# PlacaBase.net
KiCad netlist of a schematic drawn in EAGLE
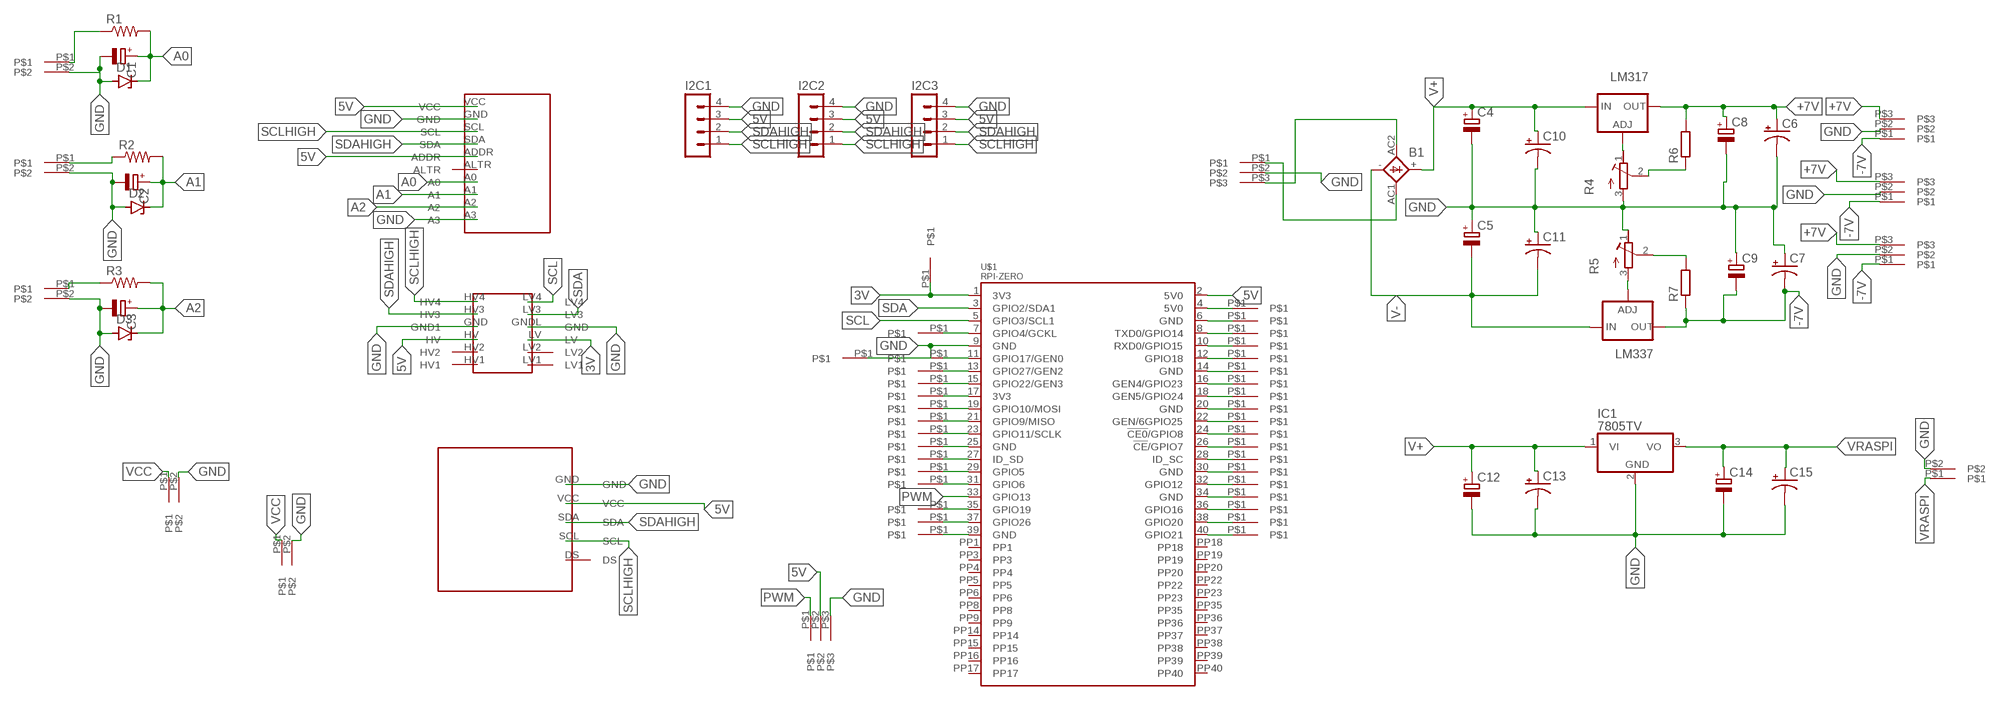
[diagram p0: schematic, sheet 1]

(export (version "E")
  (design (tool "Eeschema 10.0.6"))
  (components
    (comp (ref "5VIN")
      (value "MOLEXPEQUEÑO2P")
      (footprint "eagle-import:MOLEXPEQUEÑO2P")
      (libsource (lib "eagle-import") (part "MOLEXPEQUEÑO2P"))
    )
    (comp (ref "B1")
      (value "KBL")
      (footprint "eagle-import:KBL")
      (libsource (lib "eagle-import") (part "KBL"))
    )
    (comp (ref "C1")
      (value "CPOL-EUE5-5")
      (footprint "eagle-import:E5-5")
      (libsource (lib "eagle-import") (part "CPOL-EUE5-5"))
    )
    (comp (ref "C2")
      (value "CPOL-EUE5-5")
      (footprint "eagle-import:E5-5")
      (libsource (lib "eagle-import") (part "CPOL-EUE5-5"))
    )
    (comp (ref "C3")
      (value "CPOL-EUE5-5")
      (footprint "eagle-import:E5-5")
      (libsource (lib "eagle-import") (part "CPOL-EUE5-5"))
    )
    (comp (ref "C4")
      (value "CPOL-EUE3.5-10")
      (footprint "eagle-import:E3,5-10")
      (libsource (lib "eagle-import") (part "R Pad Grand_CPOL-EUE3.5-10"))
    )
    (comp (ref "C5")
      (value "CPOL-EUE3.5-10")
      (footprint "eagle-import:E3,5-10")
      (libsource (lib "eagle-import") (part "R Pad Grand_CPOL-EUE3.5-10"))
    )
    (comp (ref "C6")
      (value "CPOL-USTAP5-45")
      (footprint "eagle-import:TAP5-45")
      (libsource (lib "eagle-import") (part "CPOL-USTAP5-45"))
    )
    (comp (ref "C7")
      (value "CPOL-USTAP5-45")
      (footprint "eagle-import:TAP5-45")
      (libsource (lib "eagle-import") (part "CPOL-USTAP5-45"))
    )
    (comp (ref "C8")
      (value "CPOL-EUTT2D7")
      (footprint "eagle-import:TT2D7")
      (libsource (lib "eagle-import") (part "R Pad Grand_CPOL-EUTT2D7"))
    )
    (comp (ref "C9")
      (value "CPOL-EUTT2D7")
      (footprint "eagle-import:TT2D7")
      (libsource (lib "eagle-import") (part "R Pad Grand_CPOL-EUTT2D7"))
    )
    (comp (ref "C10")
      (value "CPOL-USTAP5-45")
      (footprint "eagle-import:TAP5-45")
      (libsource (lib "eagle-import") (part "CPOL-USTAP5-45"))
    )
    (comp (ref "C11")
      (value "CPOL-USTAP5-45")
      (footprint "eagle-import:TAP5-45")
      (libsource (lib "eagle-import") (part "CPOL-USTAP5-45"))
    )
    (comp (ref "C12")
      (value "CPOL-EUE3.5-10")
      (footprint "eagle-import:E3,5-10")
      (libsource (lib "eagle-import") (part "R Pad Grand_CPOL-EUE3.5-10"))
    )
    (comp (ref "C13")
      (value "CPOL-USTAP5-45")
      (footprint "eagle-import:TAP5-45")
      (libsource (lib "eagle-import") (part "CPOL-USTAP5-45"))
    )
    (comp (ref "C14")
      (value "CPOL-EUTT2D7")
      (footprint "eagle-import:TT2D7")
      (libsource (lib "eagle-import") (part "R Pad Grand_CPOL-EUTT2D7"))
    )
    (comp (ref "C15")
      (value "CPOL-USTAP5-45")
      (footprint "eagle-import:TAP5-45")
      (libsource (lib "eagle-import") (part "CPOL-USTAP5-45"))
    )
    (comp (ref "D1")
      (value "ZENER-DIODEDO34-7")
      (footprint "eagle-import:DO34Z7")
      (libsource (lib "eagle-import") (part "ZENER-DIODEDO34-7"))
    )
    (comp (ref "D2")
      (value "ZENER-DIODEDO34-7")
      (footprint "eagle-import:DO34Z7")
      (libsource (lib "eagle-import") (part "ZENER-DIODEDO34-7"))
    )
    (comp (ref "D3")
      (value "ZENER-DIODEDO34-7")
      (footprint "eagle-import:DO34Z7")
      (libsource (lib "eagle-import") (part "ZENER-DIODEDO34-7"))
    )
    (comp (ref "ENTRADAAC")
      (value "MOLEXPEQUEÑO")
      (footprint "eagle-import:MOLEXPEQUEÑO")
      (libsource (lib "eagle-import") (part "MOLEXPEQUEÑO"))
    )
    (comp (ref "I2C1")
      (value "MA04-1")
      (footprint "eagle-import:MA04-1")
      (libsource (lib "eagle-import") (part "MA04-1"))
    )
    (comp (ref "I2C2")
      (value "MA04-1")
      (footprint "eagle-import:MA04-1")
      (libsource (lib "eagle-import") (part "MA04-1"))
    )
    (comp (ref "I2C3")
      (value "MA04-1")
      (footprint "eagle-import:MA04-1")
      (libsource (lib "eagle-import") (part "MA04-1"))
    )
    (comp (ref "IC1")
      (value "7805TV")
      (footprint "eagle-import:TO220V")
      (libsource (lib "eagle-import") (part "78TV05"))
    )
    (comp (ref "LM317")
      (value "LM317TS")
      (footprint "eagle-import:317TS")
      (libsource (lib "eagle-import") (part "LM317TS"))
    )
    (comp (ref "LM337")
      (value "LM337TS")
      (footprint "eagle-import:337TS")
      (libsource (lib "eagle-import") (part "LM337TS"))
    )
    (comp (ref "R1")
      (value "R-US_0204/5")
      (footprint "eagle-import:0204_5")
      (libsource (lib "eagle-import") (part "R-US_0204/5"))
    )
    (comp (ref "R2")
      (value "R-US_0204/5")
      (footprint "eagle-import:0204_5")
      (libsource (lib "eagle-import") (part "R-US_0204/5"))
    )
    (comp (ref "R3")
      (value "R-US_0204/5")
      (footprint "eagle-import:0204_5")
      (libsource (lib "eagle-import") (part "R-US_0204/5"))
    )
    (comp (ref "R4")
      (value "R-TRIMMT93YA")
      (footprint "eagle-import:RTRIMT93YA")
      (libsource (lib "eagle-import") (part "R-TRIMMT93YA"))
    )
    (comp (ref "R5")
      (value "R-TRIMMT93YA")
      (footprint "eagle-import:RTRIMT93YA")
      (libsource (lib "eagle-import") (part "R-TRIMMT93YA"))
    )
    (comp (ref "R6")
      (value "R-EU_0207/7")
      (footprint "eagle-import:0207_7")
      (libsource (lib "eagle-import") (part "R-EU_0207/7"))
    )
    (comp (ref "R7")
      (value "R-EU_0207/7")
      (footprint "eagle-import:0207_7")
      (libsource (lib "eagle-import") (part "R-EU_0207/7"))
    )
    (comp (ref "U$1")
      (value "RPI-ZERO")
      (footprint "eagle-import:RASP_PI_ZERO_BOARD_FULL")
      (libsource (lib "eagle-import") (part "RPI-ZERO"))
    )
    (comp (ref "U$2")
      (value "ADS1115")
      (footprint "eagle-import:ADS1115")
      (libsource (lib "eagle-import") (part "ADS1115"))
    )
    (comp (ref "U$3")
      (value "RTC1307")
      (footprint "eagle-import:RTC1307")
      (libsource (lib "eagle-import") (part "RTC1307"))
    )
    (comp (ref "U$4")
      (value "CONVERSORLOGICO")
      (footprint "eagle-import:CONVERSORLOGICO")
      (libsource (lib "eagle-import") (part "CONVERSORLOGICO"))
    )
    (comp (ref "U$5")
      (value "MOLEXPEQUEÑO")
      (footprint "eagle-import:MOLEXPEQUEÑO")
      (libsource (lib "eagle-import") (part "MOLEXPEQUEÑO"))
    )
    (comp (ref "U$6")
      (value "MOLEXPEQUEÑO2P")
      (footprint "eagle-import:MOLEXPEQUEÑO2P")
      (libsource (lib "eagle-import") (part "MOLEXPEQUEÑO2P"))
    )
    (comp (ref "U$7")
      (value "MOLEXPEQUEÑO2P")
      (footprint "eagle-import:MOLEXPEQUEÑO2P")
      (libsource (lib "eagle-import") (part "MOLEXPEQUEÑO2P"))
    )
    (comp (ref "U$8")
      (value "MOLEXPEQUEÑO2P")
      (footprint "eagle-import:MOLEXPEQUEÑO2P")
      (libsource (lib "eagle-import") (part "MOLEXPEQUEÑO2P"))
    )
    (comp (ref "U$9")
      (value "MOLEXPEQUEÑO2P")
      (footprint "eagle-import:MOLEXPEQUEÑO2P")
      (libsource (lib "eagle-import") (part "MOLEXPEQUEÑO2P"))
    )
    (comp (ref "U$10")
      (value "MOLEXPEQUEÑO2P")
      (footprint "eagle-import:MOLEXPEQUEÑO2P")
      (libsource (lib "eagle-import") (part "MOLEXPEQUEÑO2P"))
    )
    (comp (ref "U$11")
      (value "PUENTE")
      (footprint "eagle-import:PUENTE")
      (libsource (lib "eagle-import") (part "PUENTE"))
    )
    (comp (ref "U$12")
      (value "PUENTE")
      (footprint "eagle-import:PUENTE")
      (libsource (lib "eagle-import") (part "PUENTE"))
    )
    (comp (ref "U$13")
      (value "MOLEXPEQUEÑO")
      (footprint "eagle-import:MOLEXPEQUEÑO")
      (libsource (lib "eagle-import") (part "MOLEXPEQUEÑO"))
    )
    (comp (ref "U$14")
      (value "MOLEXPEQUEÑO")
      (footprint "eagle-import:MOLEXPEQUEÑO")
      (libsource (lib "eagle-import") (part "MOLEXPEQUEÑO"))
    )
    (comp (ref "U$15")
      (value "MOLEXPEQUEÑO")
      (footprint "eagle-import:MOLEXPEQUEÑO")
      (libsource (lib "eagle-import") (part "MOLEXPEQUEÑO"))
    )
    (comp (ref "U$16")
      (value "PUENTE")
      (footprint "eagle-import:PUENTE")
      (libsource (lib "eagle-import") (part "PUENTE"))
    )
    (comp (ref "U$17")
      (value "PUENTE")
      (footprint "eagle-import:PUENTE")
      (libsource (lib "eagle-import") (part "PUENTE"))
    )
    (comp (ref "U$18")
      (value "PUENTE")
      (footprint "eagle-import:PUENTE")
      (libsource (lib "eagle-import") (part "PUENTE"))
    )
    (comp (ref "U$19")
      (value "PUENTE")
      (footprint "eagle-import:PUENTE")
      (libsource (lib "eagle-import") (part "PUENTE"))
    )
    (comp (ref "U$20")
      (value "PUENTE")
      (footprint "eagle-import:PUENTE")
      (libsource (lib "eagle-import") (part "PUENTE"))
    )
    (comp (ref "U$21")
      (value "PUENTE")
      (footprint "eagle-import:PUENTE")
      (libsource (lib "eagle-import") (part "PUENTE"))
    )
    (comp (ref "U$22")
      (value "PUENTE")
      (footprint "eagle-import:PUENTE")
      (libsource (lib "eagle-import") (part "PUENTE"))
    )
    (comp (ref "U$23")
      (value "PUENTE")
      (footprint "eagle-import:PUENTE")
      (libsource (lib "eagle-import") (part "PUENTE"))
    )
    (comp (ref "U$24")
      (value "PUENTE")
      (footprint "eagle-import:PUENTE")
      (libsource (lib "eagle-import") (part "PUENTE"))
    )
    (comp (ref "U$25")
      (value "PUENTE")
      (footprint "eagle-import:PUENTE")
      (libsource (lib "eagle-import") (part "PUENTE"))
    )
    (comp (ref "U$26")
      (value "PUENTE")
      (footprint "eagle-import:PUENTE")
      (libsource (lib "eagle-import") (part "PUENTE"))
    )
    (comp (ref "U$27")
      (value "PUENTE")
      (footprint "eagle-import:PUENTE")
      (libsource (lib "eagle-import") (part "PUENTE"))
    )
    (comp (ref "U$28")
      (value "PUENTE")
      (footprint "eagle-import:PUENTE")
      (libsource (lib "eagle-import") (part "PUENTE"))
    )
    (comp (ref "U$29")
      (value "PUENTE")
      (footprint "eagle-import:PUENTE")
      (libsource (lib "eagle-import") (part "PUENTE"))
    )
    (comp (ref "U$30")
      (value "PUENTE")
      (footprint "eagle-import:PUENTE")
      (libsource (lib "eagle-import") (part "PUENTE"))
    )
    (comp (ref "U$31")
      (value "PUENTE")
      (footprint "eagle-import:PUENTE")
      (libsource (lib "eagle-import") (part "PUENTE"))
    )
    (comp (ref "U$32")
      (value "PUENTE")
      (footprint "eagle-import:PUENTE")
      (libsource (lib "eagle-import") (part "PUENTE"))
    )
    (comp (ref "U$33")
      (value "PUENTE")
      (footprint "eagle-import:PUENTE")
      (libsource (lib "eagle-import") (part "PUENTE"))
    )
    (comp (ref "U$34")
      (value "PUENTE")
      (footprint "eagle-import:PUENTE")
      (libsource (lib "eagle-import") (part "PUENTE"))
    )
    (comp (ref "U$35")
      (value "PUENTE")
      (footprint "eagle-import:PUENTE")
      (libsource (lib "eagle-import") (part "PUENTE"))
    )
    (comp (ref "U$36")
      (value "PUENTE")
      (footprint "eagle-import:PUENTE")
      (libsource (lib "eagle-import") (part "PUENTE"))
    )
    (comp (ref "U$37")
      (value "PUENTE")
      (footprint "eagle-import:PUENTE")
      (libsource (lib "eagle-import") (part "PUENTE"))
    )
    (comp (ref "U$38")
      (value "PUENTE")
      (footprint "eagle-import:PUENTE")
      (libsource (lib "eagle-import") (part "PUENTE"))
    )
    (comp (ref "U$39")
      (value "PUENTE")
      (footprint "eagle-import:PUENTE")
      (libsource (lib "eagle-import") (part "PUENTE"))
    )
    (comp (ref "U$40")
      (value "PUENTE")
      (footprint "eagle-import:PUENTE")
      (libsource (lib "eagle-import") (part "PUENTE"))
    )
    (comp (ref "U$41")
      (value "PUENTE")
      (footprint "eagle-import:PUENTE")
      (libsource (lib "eagle-import") (part "PUENTE"))
    )
    (comp (ref "U$42")
      (value "PUENTE")
      (footprint "eagle-import:PUENTE")
      (libsource (lib "eagle-import") (part "PUENTE"))
    )
    (comp (ref "U$43")
      (value "PUENTE")
      (footprint "eagle-import:PUENTE")
      (libsource (lib "eagle-import") (part "PUENTE"))
    )
    (comp (ref "U$44")
      (value "PUENTE")
      (footprint "eagle-import:PUENTE")
      (libsource (lib "eagle-import") (part "PUENTE"))
    )
    (comp (ref "U$45")
      (value "PUENTE")
      (footprint "eagle-import:PUENTE")
      (libsource (lib "eagle-import") (part "PUENTE"))
    )
    (comp (ref "U$46")
      (value "PUENTE")
      (footprint "eagle-import:PUENTE")
      (libsource (lib "eagle-import") (part "PUENTE"))
    )
    (comp (ref "U$47")
      (value "PUENTE")
      (footprint "eagle-import:PUENTE")
      (libsource (lib "eagle-import") (part "PUENTE"))
    )
    (comp (ref "U$48")
      (value "PUENTE")
      (footprint "eagle-import:PUENTE")
      (libsource (lib "eagle-import") (part "PUENTE"))
    )
    (comp (ref "U$49")
      (value "PUENTE")
      (footprint "eagle-import:PUENTE")
      (libsource (lib "eagle-import") (part "PUENTE"))
    )
  )
  (nets
    (net (code "1") (name "+7V") (class "Default")
      (node (ref "C6") (pin "+") (pinfunction "+_+") (pintype "passive"))
      (node (ref "C8") (pin "+") (pinfunction "+_+") (pintype "passive"))
      (node (ref "LM317") (pin "2") (pinfunction "OUT_2") (pintype "passive"))
      (node (ref "R6") (pin "2") (pinfunction "2_2") (pintype "passive"))
      (node (ref "U$13") (pin "P$3") (pinfunction "P$3_P$3") (pintype "bidirectional"))
      (node (ref "U$14") (pin "P$3") (pinfunction "P$3_P$3") (pintype "bidirectional"))
      (node (ref "U$15") (pin "P$3") (pinfunction "P$3_P$3") (pintype "bidirectional"))
    )
    (net (code "2") (name "-7V") (class "Default")
      (node (ref "C7") (pin "-") (pinfunction "-_-") (pintype "passive"))
      (node (ref "C9") (pin "-") (pinfunction "-_-") (pintype "passive"))
      (node (ref "LM337") (pin "3") (pinfunction "OUT_3") (pintype "passive"))
      (node (ref "R7") (pin "1") (pinfunction "1_1") (pintype "passive"))
      (node (ref "U$13") (pin "P$1") (pinfunction "P$1_P$1") (pintype "bidirectional"))
      (node (ref "U$14") (pin "P$1") (pinfunction "P$1_P$1") (pintype "bidirectional"))
      (node (ref "U$15") (pin "P$1") (pinfunction "P$1_P$1") (pintype "bidirectional"))
    )
    (net (code "3") (name "3V") (class "Default")
      (node (ref "U$1") (pin "1") (pinfunction "3V3_1") (pintype "power_in"))
      (node (ref "U$4") (pin "LV") (pinfunction "LV_LV") (pintype "bidirectional"))
      (node (ref "U$48") (pin "P$1") (pinfunction "P$1_P$1") (pintype "bidirectional"))
    )
    (net (code "4") (name "5V") (class "Default")
      (node (ref "I2C1") (pin "3") (pinfunction "3_3") (pintype "passive"))
      (node (ref "I2C2") (pin "3") (pinfunction "3_3") (pintype "passive"))
      (node (ref "I2C3") (pin "3") (pinfunction "3_3") (pintype "passive"))
      (node (ref "U$1") (pin "2") (pinfunction "5V0_2") (pintype "power_in"))
      (node (ref "U$2") (pin "ADDR") (pinfunction "ADDR_ADDR") (pintype "bidirectional"))
      (node (ref "U$2") (pin "VCC") (pinfunction "VCC_VCC") (pintype "bidirectional"))
      (node (ref "U$3") (pin "VCC") (pinfunction "VCC_VCC") (pintype "bidirectional"))
      (node (ref "U$4") (pin "HV") (pinfunction "HV_HV") (pintype "bidirectional"))
      (node (ref "U$5") (pin "P$2") (pinfunction "P$2_P$2") (pintype "bidirectional"))
    )
    (net (code "5") (name "A0") (class "Default")
      (node (ref "C1") (pin "+") (pinfunction "+_+") (pintype "passive"))
      (node (ref "D1") (pin "C") (pinfunction "C_C") (pintype "passive"))
      (node (ref "R1") (pin "2") (pinfunction "2_2") (pintype "passive"))
      (node (ref "U$2") (pin "A0") (pinfunction "A0_A0") (pintype "bidirectional"))
    )
    (net (code "6") (name "A1") (class "Default")
      (node (ref "C2") (pin "+") (pinfunction "+_+") (pintype "passive"))
      (node (ref "D2") (pin "C") (pinfunction "C_C") (pintype "passive"))
      (node (ref "R2") (pin "2") (pinfunction "2_2") (pintype "passive"))
      (node (ref "U$2") (pin "A1") (pinfunction "A1_A1") (pintype "bidirectional"))
    )
    (net (code "7") (name "A2") (class "Default")
      (node (ref "C3") (pin "+") (pinfunction "+_+") (pintype "passive"))
      (node (ref "D3") (pin "C") (pinfunction "C_C") (pintype "passive"))
      (node (ref "R3") (pin "2") (pinfunction "2_2") (pintype "passive"))
      (node (ref "U$2") (pin "A2") (pinfunction "A2_A2") (pintype "bidirectional"))
    )
    (net (code "8") (name "GND") (class "Default")
      (node (ref "5VIN") (pin "P$2") (pinfunction "P$2_P$2") (pintype "bidirectional"))
      (node (ref "C1") (pin "-") (pinfunction "-_-") (pintype "passive"))
      (node (ref "C10") (pin "-") (pinfunction "-_-") (pintype "passive"))
      (node (ref "C11") (pin "+") (pinfunction "+_+") (pintype "passive"))
      (node (ref "C12") (pin "-") (pinfunction "-_-") (pintype "passive"))
      (node (ref "C13") (pin "-") (pinfunction "-_-") (pintype "passive"))
      (node (ref "C14") (pin "-") (pinfunction "-_-") (pintype "passive"))
      (node (ref "C15") (pin "-") (pinfunction "-_-") (pintype "passive"))
      (node (ref "C2") (pin "-") (pinfunction "-_-") (pintype "passive"))
      (node (ref "C3") (pin "-") (pinfunction "-_-") (pintype "passive"))
      (node (ref "C4") (pin "-") (pinfunction "-_-") (pintype "passive"))
      (node (ref "C5") (pin "+") (pinfunction "+_+") (pintype "passive"))
      (node (ref "C6") (pin "-") (pinfunction "-_-") (pintype "passive"))
      (node (ref "C7") (pin "+") (pinfunction "+_+") (pintype "passive"))
      (node (ref "C8") (pin "-") (pinfunction "-_-") (pintype "passive"))
      (node (ref "C9") (pin "+") (pinfunction "+_+") (pintype "passive"))
      (node (ref "D1") (pin "A") (pinfunction "A_A") (pintype "passive"))
      (node (ref "D2") (pin "A") (pinfunction "A_A") (pintype "passive"))
      (node (ref "D3") (pin "A") (pinfunction "A_A") (pintype "passive"))
      (node (ref "ENTRADAAC") (pin "P$2") (pinfunction "P$2_P$2") (pintype "bidirectional"))
      (node (ref "I2C1") (pin "4") (pinfunction "4_4") (pintype "passive"))
      (node (ref "I2C2") (pin "4") (pinfunction "4_4") (pintype "passive"))
      (node (ref "I2C3") (pin "4") (pinfunction "4_4") (pintype "passive"))
      (node (ref "IC1") (pin "2") (pinfunction "GND_2") (pintype "passive"))
      (node (ref "R4") (pin "3") (pinfunction "A_3") (pintype "passive"))
      (node (ref "R5") (pin "1") (pinfunction "E_1") (pintype "passive"))
      (node (ref "U$1") (pin "9") (pinfunction "GND_9") (pintype "power_in"))
      (node (ref "U$10") (pin "P$2") (pinfunction "P$2_P$2") (pintype "bidirectional"))
      (node (ref "U$13") (pin "P$2") (pinfunction "P$2_P$2") (pintype "bidirectional"))
      (node (ref "U$14") (pin "P$2") (pinfunction "P$2_P$2") (pintype "bidirectional"))
      (node (ref "U$15") (pin "P$2") (pinfunction "P$2_P$2") (pintype "bidirectional"))
      (node (ref "U$2") (pin "A3") (pinfunction "A3_A3") (pintype "bidirectional"))
      (node (ref "U$2") (pin "GND") (pinfunction "GND_GND") (pintype "bidirectional"))
      (node (ref "U$3") (pin "GND") (pinfunction "GND_GND") (pintype "bidirectional"))
      (node (ref "U$4") (pin "GND") (pinfunction "GND1_GND") (pintype "bidirectional"))
      (node (ref "U$4") (pin "GNDL") (pinfunction "GND_GNDL") (pintype "bidirectional"))
      (node (ref "U$49") (pin "P$1") (pinfunction "P$1_P$1") (pintype "bidirectional"))
      (node (ref "U$5") (pin "P$3") (pinfunction "P$3_P$3") (pintype "bidirectional"))
      (node (ref "U$6") (pin "P$2") (pinfunction "P$2_P$2") (pintype "bidirectional"))
      (node (ref "U$7") (pin "P$2") (pinfunction "P$2_P$2") (pintype "bidirectional"))
      (node (ref "U$8") (pin "P$2") (pinfunction "P$2_P$2") (pintype "bidirectional"))
      (node (ref "U$9") (pin "P$2") (pinfunction "P$2_P$2") (pintype "bidirectional"))
    )
    (net (code "9") (name "Net-(B1-AC1)") (class "Default")
      (node (ref "B1") (pin "AC2") (pinfunction "AC1_AC2") (pintype "passive"))
      (node (ref "ENTRADAAC") (pin "P$3") (pinfunction "P$3_P$3") (pintype "bidirectional"))
    )
    (net (code "10") (name "Net-(B1-AC2)") (class "Default")
      (node (ref "B1") (pin "AC1") (pinfunction "AC2_AC1") (pintype "passive"))
      (node (ref "ENTRADAAC") (pin "P$1") (pinfunction "P$1_P$1") (pintype "bidirectional"))
    )
    (net (code "11") (name "Net-(LM317-ADJ)") (class "Default")
      (node (ref "LM317") (pin "1") (pinfunction "ADJ_1") (pintype "input"))
      (node (ref "R4") (pin "1") (pinfunction "E_1") (pintype "passive"))
    )
    (net (code "12") (name "Net-(LM337-ADJ)") (class "Default")
      (node (ref "LM337") (pin "1") (pinfunction "ADJ_1") (pintype "input"))
      (node (ref "R5") (pin "3") (pinfunction "A_3") (pintype "passive"))
    )
    (net (code "13") (name "Net-(R1-Pad1)") (class "Default")
      (node (ref "R1") (pin "1") (pinfunction "1_1") (pintype "passive"))
      (node (ref "U$6") (pin "P$1") (pinfunction "P$1_P$1") (pintype "bidirectional"))
    )
    (net (code "14") (name "Net-(R2-Pad1)") (class "Default")
      (node (ref "R2") (pin "1") (pinfunction "1_1") (pintype "passive"))
      (node (ref "U$7") (pin "P$1") (pinfunction "P$1_P$1") (pintype "bidirectional"))
    )
    (net (code "15") (name "Net-(R3-Pad1)") (class "Default")
      (node (ref "R3") (pin "1") (pinfunction "1_1") (pintype "passive"))
      (node (ref "U$8") (pin "P$1") (pinfunction "P$1_P$1") (pintype "bidirectional"))
    )
    (net (code "16") (name "Net-(R4-S)") (class "Default")
      (node (ref "R4") (pin "2") (pinfunction "S_2") (pintype "passive"))
      (node (ref "R6") (pin "1") (pinfunction "1_1") (pintype "passive"))
    )
    (net (code "17") (name "Net-(R5-S)") (class "Default")
      (node (ref "R5") (pin "2") (pinfunction "S_2") (pintype "passive"))
      (node (ref "R7") (pin "2") (pinfunction "2_2") (pintype "passive"))
    )
    (net (code "18") (name "Net-(U$1-3V3-Pad17)") (class "Default")
      (node (ref "U$1") (pin "17") (pinfunction "3V3_17") (pintype "power_in"))
      (node (ref "U$17") (pin "P$1") (pinfunction "P$1_P$1") (pintype "bidirectional"))
    )
    (net (code "19") (name "Net-(U$1-5V0-Pad4)") (class "Default")
      (node (ref "U$1") (pin "4") (pinfunction "5V0_4") (pintype "power_in"))
      (node (ref "U$46") (pin "P$1") (pinfunction "P$1_P$1") (pintype "bidirectional"))
    )
    (net (code "20") (name "Net-(U$1-GEN4{slash}GPIO23)") (class "Default")
      (node (ref "U$1") (pin "16") (pinfunction "GEN4/GPIO23_16") (pintype "bidirectional"))
      (node (ref "U$30") (pin "P$1") (pinfunction "P$1_P$1") (pintype "bidirectional"))
    )
    (net (code "21") (name "Net-(U$1-GEN5{slash}GPIO24)") (class "Default")
      (node (ref "U$1") (pin "18") (pinfunction "GEN5/GPIO24_18") (pintype "bidirectional"))
      (node (ref "U$31") (pin "P$1") (pinfunction "P$1_P$1") (pintype "bidirectional"))
    )
    (net (code "22") (name "Net-(U$1-GEN{slash}6GPIO25)") (class "Default")
      (node (ref "U$1") (pin "22") (pinfunction "GEN/6GPIO25_22") (pintype "bidirectional"))
      (node (ref "U$33") (pin "P$1") (pinfunction "P$1_P$1") (pintype "bidirectional"))
    )
    (net (code "23") (name "Net-(U$1-GND-Pad6)") (class "Default")
      (node (ref "U$1") (pin "6") (pinfunction "GND_6") (pintype "power_in"))
      (node (ref "U$25") (pin "P$1") (pinfunction "P$1_P$1") (pintype "bidirectional"))
    )
    (net (code "24") (name "Net-(U$1-GND-Pad14)") (class "Default")
      (node (ref "U$1") (pin "14") (pinfunction "GND_14") (pintype "power_in"))
      (node (ref "U$29") (pin "P$1") (pinfunction "P$1_P$1") (pintype "bidirectional"))
    )
    (net (code "25") (name "Net-(U$1-GND-Pad20)") (class "Default")
      (node (ref "U$1") (pin "20") (pinfunction "GND_20") (pintype "power_in"))
      (node (ref "U$32") (pin "P$1") (pinfunction "P$1_P$1") (pintype "bidirectional"))
    )
    (net (code "26") (name "Net-(U$1-GND-Pad25)") (class "Default")
      (node (ref "U$1") (pin "25") (pinfunction "GND_25") (pintype "power_in"))
      (node (ref "U$21") (pin "P$1") (pinfunction "P$1_P$1") (pintype "bidirectional"))
    )
    (net (code "27") (name "Net-(U$1-GND-Pad30)") (class "Default")
      (node (ref "U$1") (pin "30") (pinfunction "GND_30") (pintype "power_in"))
      (node (ref "U$37") (pin "P$1") (pinfunction "P$1_P$1") (pintype "bidirectional"))
    )
    (net (code "28") (name "Net-(U$1-GND-Pad34)") (class "Default")
      (node (ref "U$1") (pin "34") (pinfunction "GND_34") (pintype "power_in"))
      (node (ref "U$39") (pin "P$1") (pinfunction "P$1_P$1") (pintype "bidirectional"))
    )
    (net (code "29") (name "Net-(U$1-GND-Pad39)") (class "Default")
      (node (ref "U$1") (pin "39") (pinfunction "GND_39") (pintype "power_in"))
      (node (ref "U$45") (pin "P$1") (pinfunction "P$1_P$1") (pintype "bidirectional"))
    )
    (net (code "30") (name "Net-(U$1-GPIO4{slash}GCKL)") (class "Default")
      (node (ref "U$1") (pin "7") (pinfunction "GPIO4/GCKL_7") (pintype "bidirectional"))
      (node (ref "U$47") (pin "P$1") (pinfunction "P$1_P$1") (pintype "bidirectional"))
    )
    (net (code "31") (name "Net-(U$1-GPIO5)") (class "Default")
      (node (ref "U$1") (pin "29") (pinfunction "GPIO5_29") (pintype "bidirectional"))
      (node (ref "U$23") (pin "P$1") (pinfunction "P$1_P$1") (pintype "bidirectional"))
    )
    (net (code "32") (name "Net-(U$1-GPIO6)") (class "Default")
      (node (ref "U$1") (pin "31") (pinfunction "GPIO6_31") (pintype "bidirectional"))
      (node (ref "U$24") (pin "P$1") (pinfunction "P$1_P$1") (pintype "bidirectional"))
    )
    (net (code "33") (name "Net-(U$1-GPIO9{slash}MISO)") (class "Default")
      (node (ref "U$1") (pin "21") (pinfunction "GPIO9/MISO_21") (pintype "bidirectional"))
      (node (ref "U$19") (pin "P$1") (pinfunction "P$1_P$1") (pintype "bidirectional"))
    )
    (net (code "34") (name "Net-(U$1-GPIO10{slash}MOSI)") (class "Default")
      (node (ref "U$1") (pin "19") (pinfunction "GPIO10/MOSI_19") (pintype "bidirectional"))
      (node (ref "U$18") (pin "P$1") (pinfunction "P$1_P$1") (pintype "bidirectional"))
    )
    (net (code "35") (name "Net-(U$1-GPIO11{slash}SCLK)") (class "Default")
      (node (ref "U$1") (pin "23") (pinfunction "GPIO11/SCLK_23") (pintype "bidirectional"))
      (node (ref "U$20") (pin "P$1") (pinfunction "P$1_P$1") (pintype "bidirectional"))
    )
    (net (code "36") (name "Net-(U$1-GPIO12)") (class "Default")
      (node (ref "U$1") (pin "32") (pinfunction "GPIO12_32") (pintype "bidirectional"))
      (node (ref "U$38") (pin "P$1") (pinfunction "P$1_P$1") (pintype "bidirectional"))
    )
    (net (code "37") (name "Net-(U$1-GPIO16)") (class "Default")
      (node (ref "U$1") (pin "36") (pinfunction "GPIO16_36") (pintype "bidirectional"))
      (node (ref "U$40") (pin "P$1") (pinfunction "P$1_P$1") (pintype "bidirectional"))
    )
    (net (code "38") (name "Net-(U$1-GPIO17{slash}GEN0)") (class "Default")
      (node (ref "U$1") (pin "11") (pinfunction "GPIO17/GEN0_11") (pintype "bidirectional"))
      (node (ref "U$11") (pin "P$1") (pinfunction "P$1_P$1") (pintype "bidirectional"))
    )
    (net (code "39") (name "Net-(U$1-GPIO18)") (class "Default")
      (node (ref "U$1") (pin "12") (pinfunction "GPIO18_12") (pintype "bidirectional"))
      (node (ref "U$28") (pin "P$1") (pinfunction "P$1_P$1") (pintype "bidirectional"))
    )
    (net (code "40") (name "Net-(U$1-GPIO19)") (class "Default")
      (node (ref "U$1") (pin "35") (pinfunction "GPIO19_35") (pintype "bidirectional"))
      (node (ref "U$43") (pin "P$1") (pinfunction "P$1_P$1") (pintype "bidirectional"))
    )
    (net (code "41") (name "Net-(U$1-GPIO20)") (class "Default")
      (node (ref "U$1") (pin "38") (pinfunction "GPIO20_38") (pintype "bidirectional"))
      (node (ref "U$41") (pin "P$1") (pinfunction "P$1_P$1") (pintype "bidirectional"))
    )
    (net (code "42") (name "Net-(U$1-GPIO21)") (class "Default")
      (node (ref "U$1") (pin "40") (pinfunction "GPIO21_40") (pintype "bidirectional"))
      (node (ref "U$42") (pin "P$1") (pinfunction "P$1_P$1") (pintype "bidirectional"))
    )
    (net (code "43") (name "Net-(U$1-GPIO22{slash}GEN3)") (class "Default")
      (node (ref "U$1") (pin "15") (pinfunction "GPIO22/GEN3_15") (pintype "bidirectional"))
      (node (ref "U$16") (pin "P$1") (pinfunction "P$1_P$1") (pintype "bidirectional"))
    )
    (net (code "44") (name "Net-(U$1-GPIO26)") (class "Default")
      (node (ref "U$1") (pin "37") (pinfunction "GPIO26_37") (pintype "bidirectional"))
      (node (ref "U$44") (pin "P$1") (pinfunction "P$1_P$1") (pintype "bidirectional"))
    )
    (net (code "45") (name "Net-(U$1-GPIO27{slash}GEN2)") (class "Default")
      (node (ref "U$1") (pin "13") (pinfunction "GPIO27/GEN2_13") (pintype "bidirectional"))
      (node (ref "U$12") (pin "P$1") (pinfunction "P$1_P$1") (pintype "bidirectional"))
    )
    (net (code "46") (name "Net-(U$1-ID_SC)") (class "Default")
      (node (ref "U$1") (pin "28") (pinfunction "ID_SC_28") (pintype "bidirectional"))
      (node (ref "U$36") (pin "P$1") (pinfunction "P$1_P$1") (pintype "bidirectional"))
    )
    (net (code "47") (name "Net-(U$1-ID_SD)") (class "Default")
      (node (ref "U$1") (pin "27") (pinfunction "ID_SD_27") (pintype "bidirectional"))
      (node (ref "U$22") (pin "P$1") (pinfunction "P$1_P$1") (pintype "bidirectional"))
    )
    (net (code "48") (name "Net-(U$1-RXD0{slash}GPIO15)") (class "Default")
      (node (ref "U$1") (pin "10") (pinfunction "RXD0/GPIO15_10") (pintype "bidirectional"))
      (node (ref "U$27") (pin "P$1") (pinfunction "P$1_P$1") (pintype "bidirectional"))
    )
    (net (code "49") (name "Net-(U$1-TXD0{slash}GPIO14)") (class "Default")
      (node (ref "U$1") (pin "8") (pinfunction "TXD0/GPIO14_8") (pintype "bidirectional"))
      (node (ref "U$26") (pin "P$1") (pinfunction "P$1_P$1") (pintype "bidirectional"))
    )
    (net (code "50") (name "Net-(U$1-~{CE0}{slash}GPIO8)") (class "Default")
      (node (ref "U$1") (pin "24") (pinfunction "~{CE0}/GPIO8_24") (pintype "bidirectional"))
      (node (ref "U$34") (pin "P$1") (pinfunction "P$1_P$1") (pintype "bidirectional"))
    )
    (net (code "51") (name "Net-(U$1-~{CE}{slash}GPIO7)") (class "Default")
      (node (ref "U$1") (pin "26") (pinfunction "~{CE}/GPIO7_26") (pintype "bidirectional"))
      (node (ref "U$35") (pin "P$1") (pinfunction "P$1_P$1") (pintype "bidirectional"))
    )
    (net (code "52") (name "PWM") (class "Default")
      (node (ref "U$1") (pin "33") (pinfunction "GPIO13_33") (pintype "bidirectional"))
      (node (ref "U$5") (pin "P$1") (pinfunction "P$1_P$1") (pintype "bidirectional"))
    )
    (net (code "53") (name "SCL") (class "Default")
      (node (ref "U$1") (pin "5") (pinfunction "GPIO3/SCL1_5") (pintype "bidirectional"))
      (node (ref "U$4") (pin "LV4") (pinfunction "LV4_LV4") (pintype "bidirectional"))
    )
    (net (code "54") (name "SCLHIGH") (class "Default")
      (node (ref "I2C1") (pin "1") (pinfunction "1_1") (pintype "passive"))
      (node (ref "I2C2") (pin "1") (pinfunction "1_1") (pintype "passive"))
      (node (ref "I2C3") (pin "1") (pinfunction "1_1") (pintype "passive"))
      (node (ref "U$2") (pin "SCL") (pinfunction "SCL_SCL") (pintype "bidirectional"))
      (node (ref "U$3") (pin "SCL") (pinfunction "SCL_SCL") (pintype "bidirectional"))
      (node (ref "U$4") (pin "HV4") (pinfunction "HV4_HV4") (pintype "bidirectional"))
    )
    (net (code "55") (name "SDA") (class "Default")
      (node (ref "U$1") (pin "3") (pinfunction "GPIO2/SDA1_3") (pintype "bidirectional"))
      (node (ref "U$4") (pin "LV3") (pinfunction "LV3_LV3") (pintype "bidirectional"))
    )
    (net (code "56") (name "SDAHIGH") (class "Default")
      (node (ref "I2C1") (pin "2") (pinfunction "2_2") (pintype "passive"))
      (node (ref "I2C2") (pin "2") (pinfunction "2_2") (pintype "passive"))
      (node (ref "I2C3") (pin "2") (pinfunction "2_2") (pintype "passive"))
      (node (ref "U$2") (pin "SDA") (pinfunction "SDA_SDA") (pintype "bidirectional"))
      (node (ref "U$3") (pin "SDA") (pinfunction "SDA_SDA") (pintype "bidirectional"))
      (node (ref "U$4") (pin "HV3") (pinfunction "HV3_HV3") (pintype "bidirectional"))
    )
    (net (code "57") (name "V+") (class "Default")
      (node (ref "B1") (pin "+") (pinfunction "+_+") (pintype "passive"))
      (node (ref "C10") (pin "+") (pinfunction "+_+") (pintype "passive"))
      (node (ref "C12") (pin "+") (pinfunction "+_+") (pintype "passive"))
      (node (ref "C13") (pin "+") (pinfunction "+_+") (pintype "passive"))
      (node (ref "C4") (pin "+") (pinfunction "+_+") (pintype "passive"))
      (node (ref "IC1") (pin "1") (pinfunction "VI_1") (pintype "input"))
      (node (ref "LM317") (pin "3") (pinfunction "IN_3") (pintype "input"))
    )
    (net (code "58") (name "V-") (class "Default")
      (node (ref "B1") (pin "-") (pinfunction "-_-") (pintype "passive"))
      (node (ref "C11") (pin "-") (pinfunction "-_-") (pintype "passive"))
      (node (ref "C5") (pin "-") (pinfunction "-_-") (pintype "passive"))
      (node (ref "LM337") (pin "2") (pinfunction "IN_2") (pintype "input"))
    )
    (net (code "59") (name "VCC") (class "Default")
      (node (ref "5VIN") (pin "P$1") (pinfunction "P$1_P$1") (pintype "bidirectional"))
      (node (ref "U$10") (pin "P$1") (pinfunction "P$1_P$1") (pintype "bidirectional"))
    )
    (net (code "60") (name "VRASPI") (class "Default")
      (node (ref "C14") (pin "+") (pinfunction "+_+") (pintype "passive"))
      (node (ref "C15") (pin "+") (pinfunction "+_+") (pintype "passive"))
      (node (ref "IC1") (pin "3") (pinfunction "VO_3") (pintype "passive"))
      (node (ref "U$9") (pin "P$1") (pinfunction "P$1_P$1") (pintype "bidirectional"))
    )
    (net (code "61") (name "unconnected-(U$1-PadPP1)") (class "Default")
      (node (ref "U$1") (pin "PP1") (pinfunction "PP1_PP1") (pintype "bidirectional"))
    )
    (net (code "62") (name "unconnected-(U$1-PadPP3)") (class "Default")
      (node (ref "U$1") (pin "PP3") (pinfunction "PP3_PP3") (pintype "bidirectional"))
    )
    (net (code "63") (name "unconnected-(U$1-PadPP4)") (class "Default")
      (node (ref "U$1") (pin "PP4") (pinfunction "PP4_PP4") (pintype "bidirectional"))
    )
    (net (code "64") (name "unconnected-(U$1-PadPP5)") (class "Default")
      (node (ref "U$1") (pin "PP5") (pinfunction "PP5_PP5") (pintype "bidirectional"))
    )
    (net (code "65") (name "unconnected-(U$1-PadPP6)") (class "Default")
      (node (ref "U$1") (pin "PP6") (pinfunction "PP6_PP6") (pintype "bidirectional"))
    )
    (net (code "66") (name "unconnected-(U$1-PadPP8)") (class "Default")
      (node (ref "U$1") (pin "PP8") (pinfunction "PP8_PP8") (pintype "bidirectional"))
    )
    (net (code "67") (name "unconnected-(U$1-PadPP9)") (class "Default")
      (node (ref "U$1") (pin "PP9") (pinfunction "PP9_PP9") (pintype "bidirectional"))
    )
    (net (code "68") (name "unconnected-(U$1-PadPP14)") (class "Default")
      (node (ref "U$1") (pin "PP14") (pinfunction "PP14_PP14") (pintype "bidirectional"))
    )
    (net (code "69") (name "unconnected-(U$1-PadPP15)") (class "Default")
      (node (ref "U$1") (pin "PP15") (pinfunction "PP15_PP15") (pintype "bidirectional"))
    )
    (net (code "70") (name "unconnected-(U$1-PadPP16)") (class "Default")
      (node (ref "U$1") (pin "PP16") (pinfunction "PP16_PP16") (pintype "bidirectional"))
    )
    (net (code "71") (name "unconnected-(U$1-PadPP17)") (class "Default")
      (node (ref "U$1") (pin "PP17") (pinfunction "PP17_PP17") (pintype "bidirectional"))
    )
    (net (code "72") (name "unconnected-(U$1-PadPP18)") (class "Default")
      (node (ref "U$1") (pin "PP18") (pinfunction "PP18_PP18") (pintype "bidirectional"))
    )
    (net (code "73") (name "unconnected-(U$1-PadPP19)") (class "Default")
      (node (ref "U$1") (pin "PP19") (pinfunction "PP19_PP19") (pintype "bidirectional"))
    )
    (net (code "74") (name "unconnected-(U$1-PadPP20)") (class "Default")
      (node (ref "U$1") (pin "PP20") (pinfunction "PP20_PP20") (pintype "open_collector"))
    )
    (net (code "75") (name "unconnected-(U$1-PadPP22)") (class "Default")
      (node (ref "U$1") (pin "PP22") (pinfunction "PP22_PP22") (pintype "bidirectional"))
    )
    (net (code "76") (name "unconnected-(U$1-PadPP23)") (class "Default")
      (node (ref "U$1") (pin "PP23") (pinfunction "PP23_PP23") (pintype "bidirectional"))
    )
    (net (code "77") (name "unconnected-(U$1-PadPP35)") (class "Default")
      (node (ref "U$1") (pin "PP35") (pinfunction "PP35_PP35") (pintype "bidirectional"))
    )
    (net (code "78") (name "unconnected-(U$1-PadPP36)") (class "Default")
      (node (ref "U$1") (pin "PP36") (pinfunction "PP36_PP36") (pintype "bidirectional"))
    )
    (net (code "79") (name "unconnected-(U$1-PadPP37)") (class "Default")
      (node (ref "U$1") (pin "PP37") (pinfunction "PP37_PP37") (pintype "bidirectional"))
    )
    (net (code "80") (name "unconnected-(U$1-PadPP38)") (class "Default")
      (node (ref "U$1") (pin "PP38") (pinfunction "PP38_PP38") (pintype "bidirectional"))
    )
    (net (code "81") (name "unconnected-(U$1-PadPP39)") (class "Default")
      (node (ref "U$1") (pin "PP39") (pinfunction "PP39_PP39") (pintype "bidirectional"))
    )
    (net (code "82") (name "unconnected-(U$1-PadPP40)") (class "Default")
      (node (ref "U$1") (pin "PP40") (pinfunction "PP40_PP40") (pintype "bidirectional"))
    )
    (net (code "83") (name "unconnected-(U$2-PadALTR)") (class "Default")
      (node (ref "U$2") (pin "ALTR") (pinfunction "ALTR_ALTR") (pintype "bidirectional"))
    )
    (net (code "84") (name "unconnected-(U$3-PadDS)") (class "Default")
      (node (ref "U$3") (pin "DS") (pinfunction "DS_DS") (pintype "bidirectional"))
    )
    (net (code "85") (name "unconnected-(U$4-PadHV1)") (class "Default")
      (node (ref "U$4") (pin "HV1") (pinfunction "HV1_HV1") (pintype "bidirectional"))
    )
    (net (code "86") (name "unconnected-(U$4-PadHV2)") (class "Default")
      (node (ref "U$4") (pin "HV2") (pinfunction "HV2_HV2") (pintype "bidirectional"))
    )
    (net (code "87") (name "unconnected-(U$4-PadLV1)") (class "Default")
      (node (ref "U$4") (pin "LV1") (pinfunction "LV1_LV1") (pintype "bidirectional"))
    )
    (net (code "88") (name "unconnected-(U$4-PadLV2)") (class "Default")
      (node (ref "U$4") (pin "LV2") (pinfunction "LV2_LV2") (pintype "bidirectional"))
    )
  )
)
